# 07_USB_Device_MicroUSB_CON.net
KiCad netlist of a schematic drawn in Altium Designer
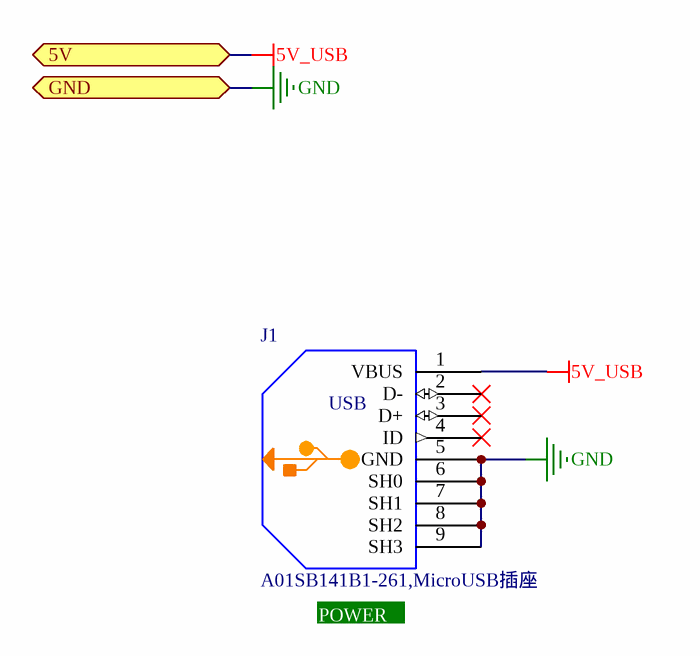
[diagram p0: 07.USB Device_MicroUSB_CON.SchDoc]

(export (version "E")
  (design (tool "Eeschema 10.0.6"))
  (components
    (comp (ref "J1")
      (value "A01SB141B1-261,MicroUSB插座")
      (footprint "MICROUSB-5S")
      (description "A01SB141B1-261,MicroUSB插座,SMT,艾立信,RoHS")
      (libsource (lib "ErpMaterialData") (part "USB_MINIB_SMT"))
    )
  )
  (nets
    (net (code "1") (name "5V_USB") (class "Default")
      (node (ref "J1") (pin "1") (pinfunction "VBUS_1") (pintype "passive"))
    )
    (net (code "2") (name "GND") (class "Default")
      (node (ref "J1") (pin "5") (pinfunction "GND_5") (pintype "power_in"))
      (node (ref "J1") (pin "6") (pinfunction "SH0_6") (pintype "passive"))
      (node (ref "J1") (pin "7") (pinfunction "SH1_7") (pintype "passive"))
      (node (ref "J1") (pin "8") (pinfunction "SH2_8") (pintype "passive"))
      (node (ref "J1") (pin "9") (pinfunction "SH3_9") (pintype "passive"))
    )
    (net (code "3") (name "unconnected-(J1-D+-Pad3)") (class "Default")
      (node (ref "J1") (pin "3") (pinfunction "D+_3") (pintype "bidirectional+no_connect"))
    )
    (net (code "4") (name "unconnected-(J1-D--Pad2)") (class "Default")
      (node (ref "J1") (pin "2") (pinfunction "D-_2") (pintype "bidirectional+no_connect"))
    )
    (net (code "5") (name "unconnected-(J1-ID-Pad4)") (class "Default")
      (node (ref "J1") (pin "4") (pinfunction "ID_4") (pintype "output+no_connect"))
    )
  )
)
